# CV2018-DIFFx1.net
KiCad netlist of a schematic drawn in Altium Designer
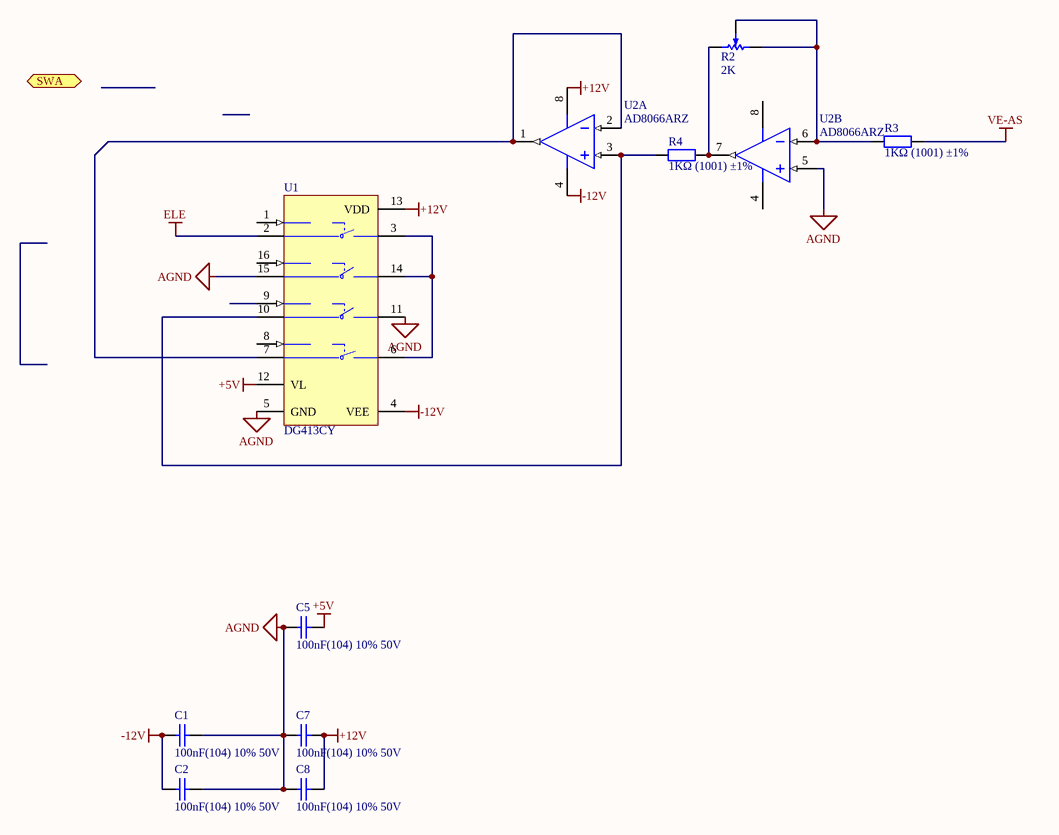
[diagram p0: CV2018-DIFFx1.SchDoc]

(export (version "E")
  (design (tool "Eeschema 10.0.6"))
  (components
    (comp (ref "C1")
      (value "100nF(104) 10% 50V")
      (footprint "LC-0805_C")
      (description "贴片电容")
      (libsource (lib "Miscellaneous Devices LC") (part "0805 100nF(104) 10% 50V"))
    )
    (comp (ref "C2")
      (value "100nF(104) 10% 50V")
      (footprint "LC-0805_C")
      (description "贴片电容")
      (libsource (lib "Miscellaneous Devices LC") (part "0805 100nF(104) 10% 50V"))
    )
    (comp (ref "C5")
      (value "100nF(104) 10% 50V")
      (footprint "LC-0805_C")
      (description "贴片电容")
      (libsource (lib "Miscellaneous Devices LC") (part "0805 100nF(104) 10% 50V"))
    )
    (comp (ref "C7")
      (value "100nF(104) 10% 50V")
      (footprint "LC-0805_C")
      (description "贴片电容")
      (libsource (lib "Miscellaneous Devices LC") (part "0805 100nF(104) 10% 50V"))
    )
    (comp (ref "C8")
      (value "100nF(104) 10% 50V")
      (footprint "LC-0805_C")
      (description "贴片电容")
      (libsource (lib "Miscellaneous Devices LC") (part "0805 100nF(104) 10% 50V"))
    )
    (comp (ref "R2")
      (value "2K")
      (footprint "POT4MM-2")
      (description "Square Trimming Potentiometer")
      (fields (field (name "PUBLISHER") "Altium Limited"))
      (libsource (lib "Miscellaneous Devices") (part "RPot SM"))
    )
    (comp (ref "R3")
      (value "1KΩ (1001) ±1%")
      (footprint "LC-0805_R")
      (description "贴片电阻")
      (libsource (lib "Miscellaneous Devices LC") (part "0805 1KΩ (1001) 1%"))
    )
    (comp (ref "R4")
      (value "1KΩ (1001) ±1%")
      (footprint "LC-0805_R")
      (description "贴片电阻")
      (libsource (lib "Miscellaneous Devices LC") (part "0805 1KΩ (1001) 1%"))
    )
    (comp (ref "U1")
      (value "DG413CY")
      (footprint "NSO16_N")
      (description "Improved, Quad, SPST Analog Switches")
      (fields (field (name "PUBLISHER") "Altium Limited"))
      (libsource (lib "Maxim Logic Switch") (part "DG413CY"))
    )
    (comp (ref "U2")
      (value "AD8066ARZ")
      (footprint "ADI-R-8_N")
      (fields (field (name "GENERIC PART NUMBER") "AD8066") (field (name "MANUFACTURER") "Analog Devices"))
      (libsource (lib "Analog Devices Operational Amplifiers") (part "AD8066ARZ"))
    )
  )
  (nets
    (net (code "1") (name "+5V") (class "Default")
      (node (ref "C5") (pin "2") (pinfunction "2_2") (pintype "passive"))
      (node (ref "U1") (pin "12") (pinfunction "VL_12") (pintype "power_in"))
    )
    (net (code "2") (name "+12V") (class "Default")
      (node (ref "C7") (pin "2") (pinfunction "2_2") (pintype "passive"))
      (node (ref "C8") (pin "2") (pinfunction "2_2") (pintype "passive"))
      (node (ref "U1") (pin "13") (pinfunction "VDD_13") (pintype "power_in"))
      (node (ref "U2") (pin "8") (pinfunction "+VS_8") (pintype "power_in"))
    )
    (net (code "3") (name "-12V") (class "Default")
      (node (ref "C1") (pin "1") (pinfunction "1_1") (pintype "passive"))
      (node (ref "C2") (pin "1") (pinfunction "1_1") (pintype "passive"))
      (node (ref "U1") (pin "4") (pinfunction "VEE_4") (pintype "power_in"))
      (node (ref "U2") (pin "4") (pinfunction "-VS_4") (pintype "power_in"))
    )
    (net (code "5") (name "AGND") (class "Default")
      (node (ref "C1") (pin "2") (pinfunction "2_2") (pintype "passive"))
      (node (ref "C2") (pin "2") (pinfunction "2_2") (pintype "passive"))
      (node (ref "C5") (pin "1") (pinfunction "1_1") (pintype "passive"))
      (node (ref "C7") (pin "1") (pinfunction "1_1") (pintype "passive"))
      (node (ref "C8") (pin "1") (pinfunction "1_1") (pintype "passive"))
      (node (ref "U1") (pin "11") (pinfunction "S3_11") (pintype "passive"))
      (node (ref "U1") (pin "15") (pinfunction "D2_15") (pintype "passive"))
      (node (ref "U1") (pin "5") (pinfunction "GND_5") (pintype "power_in"))
      (node (ref "U2") (pin "5") (pinfunction "+IN_2_5") (pintype "input"))
    )
    (net (code "6") (name "ELE") (class "Default")
      (node (ref "U1") (pin "2") (pinfunction "D1_2") (pintype "passive"))
    )
    (net (code "7") (name "Net-(R2-+)") (class "Default")
      (node (ref "R2") (pin "CW") (pinfunction "+_CW") (pintype "passive"))
      (node (ref "R4") (pin "2") (pinfunction "2_2") (pintype "passive"))
      (node (ref "U2") (pin "7") (pinfunction "VOUT_2_7") (pintype "output"))
    )
    (net (code "8") (name "Net-(R2--)") (class "Default")
      (node (ref "R2") (pin "CCW") (pinfunction "-_CCW") (pintype "passive"))
      (node (ref "R2") (pin "W") (pinfunction "W_W") (pintype "passive"))
      (node (ref "R3") (pin "1") (pinfunction "1_1") (pintype "passive"))
      (node (ref "U2") (pin "6") (pinfunction "-IN_2_6") (pintype "input"))
    )
    (net (code "9") (name "Net-(U1-D3)") (class "Default")
      (node (ref "R4") (pin "1") (pinfunction "1_1") (pintype "passive"))
      (node (ref "U1") (pin "10") (pinfunction "D3_10") (pintype "passive"))
      (node (ref "U2") (pin "3") (pinfunction "+IN_1_3") (pintype "input"))
    )
    (net (code "10") (name "Net-(U1-D4)") (class "Default")
      (node (ref "U1") (pin "7") (pinfunction "D4_7") (pintype "passive"))
      (node (ref "U2") (pin "1") (pinfunction "VOUT_1_1") (pintype "output"))
      (node (ref "U2") (pin "2") (pinfunction "-IN_1_2") (pintype "input"))
    )
    (net (code "11") (name "Net-(U1-S1)") (class "Default")
      (node (ref "U1") (pin "14") (pinfunction "S2_14") (pintype "passive"))
      (node (ref "U1") (pin "3") (pinfunction "S1_3") (pintype "passive"))
      (node (ref "U1") (pin "6") (pinfunction "S4_6") (pintype "passive"))
    )
    (net (code "12") (name "VE-AS") (class "Default")
      (node (ref "R3") (pin "2") (pinfunction "2_2") (pintype "passive"))
    )
    (net (code "13") (name "unconnected-(U1-IN1-Pad1)") (class "Default")
      (node (ref "U1") (pin "1") (pinfunction "IN1_1") (pintype "input"))
    )
    (net (code "14") (name "unconnected-(U1-IN2-Pad16)") (class "Default")
      (node (ref "U1") (pin "16") (pinfunction "IN2_16") (pintype "input"))
    )
    (net (code "15") (name "unconnected-(U1-IN3-Pad9)") (class "Default")
      (node (ref "U1") (pin "9") (pinfunction "IN3_9") (pintype "input"))
    )
    (net (code "16") (name "unconnected-(U1-IN_4-Pad8)") (class "Default")
      (node (ref "U1") (pin "8") (pinfunction "IN_4_8") (pintype "input"))
    )
    (net (code "17") (name "unconnected-(U2B-+VS-Pad8)") (class "Default")
      (node (ref "U2") (pin "8") (pinfunction "+VS_8") (pintype "power_in"))
    )
    (net (code "18") (name "unconnected-(U2B--VS-Pad4)") (class "Default")
      (node (ref "U2") (pin "4") (pinfunction "-VS_4") (pintype "power_in"))
    )
  )
)
